# DSPcontrol.net
KiCad netlist of a schematic drawn in Altium Designer
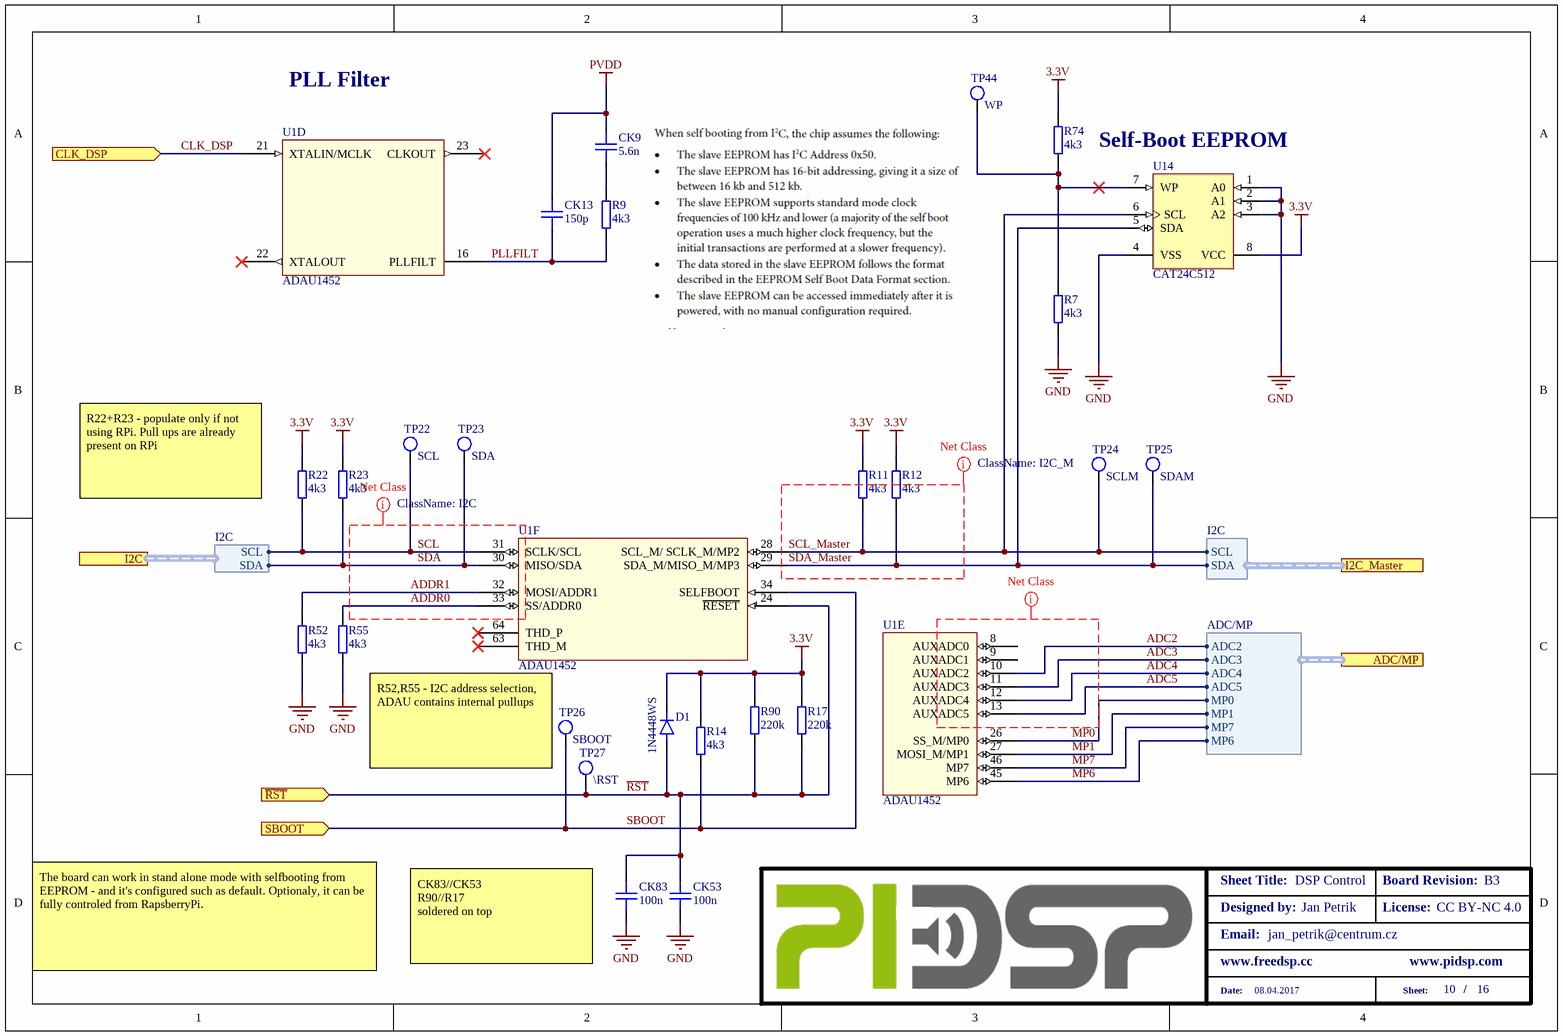
[diagram p0: DSPcontrol.SchDoc]

(export (version "E")
  (design (tool "Eeschema 10.0.6"))
  (components
    (comp (ref "CK9")
      (value "5.6n")
      (footprint "CAPC1608X09N(SMC0603)")
      (description "MLCC")
      (fields
        (field (name "TOLERANCE") "10%")
        (field (name "VOLTAGE") "50V")
        (field (name "AUTHOR") "JP/27.03.2014")
      )
      (libsource (lib "JP_C") (part "5.6n-50V-0603-X7R"))
    )
    (comp (ref "CK13")
      (value "150p")
      (footprint "CAPC1608X09N(SMC0603)")
      (description "MLCC")
      (fields
        (field (name "TOLERANCE") "10%")
        (field (name "VOLTAGE") "50V")
        (field (name "AUTHOR") "JP/27.03.2014")
      )
      (libsource (lib "JP_C") (part "150p-50V-0603-NP0"))
    )
    (comp (ref "CK53")
      (value "100n")
      (footprint "CAPC1608X09N(SMC0603)")
      (description "MLCC")
      (fields
        (field (name "VOLTAGE") "50V")
        (field (name "TOLERANCE") "10%")
        (field (name "AUTHOR") "JP/27.03.2014")
      )
      (libsource (lib "JP_C") (part "100n-50V-0603-X7R"))
    )
    (comp (ref "CK83")
      (value "100n")
      (footprint "CAPC1608X09N(SMC0603)")
      (description "MLCC")
      (fields
        (field (name "VOLTAGE") "50V")
        (field (name "TOLERANCE") "10%")
        (field (name "AUTHOR") "JP/27.03.2014")
      )
      (libsource (lib "JP_C") (part "100n-50V-0603-X7R"))
    )
    (comp (ref "D1")
      (value "1N4448WS")
      (footprint "SOD-323")
      (description "Small signal diode")
      (fields (field (name "VOLTAGE") "75V"))
      (libsource (lib "JP_IC") (part "1N4448WS"))
    )
    (comp (ref "R7")
      (value "4k3")
      (footprint "RESC1608X06N(SMR0603)")
      (description "Chip Resistor")
      (fields (field (name "AUTHOR") "JP/10.06.2014"))
      (libsource (lib "JP_R") (part "4K3-100mW-0603-ThickFilm"))
    )
    (comp (ref "R9")
      (value "4k3")
      (footprint "RESC1608X06N(SMR0603)")
      (description "Chip Resistor")
      (fields (field (name "AUTHOR") "JP/10.06.2014"))
      (libsource (lib "JP_R") (part "4K3-100mW-0603-ThickFilm"))
    )
    (comp (ref "R11")
      (value "4k3")
      (footprint "RESC1608X06N(SMR0603)")
      (description "Chip Resistor")
      (fields (field (name "AUTHOR") "JP/10.06.2014"))
      (libsource (lib "JP_R") (part "4K3-100mW-0603-ThickFilm"))
    )
    (comp (ref "R12")
      (value "4k3")
      (footprint "RESC1608X06N(SMR0603)")
      (description "Chip Resistor")
      (fields (field (name "AUTHOR") "JP/10.06.2014"))
      (libsource (lib "JP_R") (part "4K3-100mW-0603-ThickFilm"))
    )
    (comp (ref "R14")
      (value "4k3")
      (footprint "RESC1608X06N(SMR0603)")
      (description "Chip Resistor")
      (fields (field (name "AUTHOR") "JP/10.06.2014"))
      (libsource (lib "JP_R") (part "4K3-100mW-0603-ThickFilm"))
    )
    (comp (ref "R17")
      (value "220k")
      (footprint "RESC1608X06N(SMR0603)")
      (description "Chip Resistor")
      (fields (field (name "AUTHOR") "JP/10.06.2014"))
      (libsource (lib "JP_R") (part "220k-100mW-0603-ThickFilm"))
    )
    (comp (ref "R22")
      (value "4k3")
      (footprint "RESC1608X06N(SMR0603)")
      (description "Chip Resistor")
      (fields (field (name "AUTHOR") "JP/10.06.2014"))
      (libsource (lib "JP_R") (part "4K3-100mW-0603-ThickFilm"))
    )
    (comp (ref "R23")
      (value "4k3")
      (footprint "RESC1608X06N(SMR0603)")
      (description "Chip Resistor")
      (fields (field (name "AUTHOR") "JP/10.06.2014"))
      (libsource (lib "JP_R") (part "4K3-100mW-0603-ThickFilm"))
    )
    (comp (ref "R52")
      (value "4k3")
      (footprint "RESC1608X06N(SMR0603)")
      (description "Chip Resistor")
      (fields (field (name "AUTHOR") "JP/10.06.2014"))
      (libsource (lib "JP_R") (part "4K3-100mW-0603-ThickFilm"))
    )
    (comp (ref "R55")
      (value "4k3")
      (footprint "RESC1608X06N(SMR0603)")
      (description "Chip Resistor")
      (fields (field (name "AUTHOR") "JP/10.06.2014"))
      (libsource (lib "JP_R") (part "4K3-100mW-0603-ThickFilm"))
    )
    (comp (ref "R74")
      (value "4k3")
      (footprint "RESC1608X06N(SMR0603)")
      (description "Chip Resistor")
      (fields (field (name "AUTHOR") "JP/10.06.2014"))
      (libsource (lib "JP_R") (part "4K3-100mW-0603-ThickFilm"))
    )
    (comp (ref "R90")
      (value "220k")
      (footprint "RESC1608X06N(SMR0603)")
      (description "Chip Resistor")
      (fields (field (name "AUTHOR") "JP/10.06.2014"))
      (libsource (lib "JP_R") (part "220k-100mW-0603-ThickFilm"))
    )
    (comp (ref "TP22")
      (value "SCL")
      (footprint "TP_0.8/0.4_ROUND")
      (description "Testpoint - VIA")
      (libsource (lib "JP_CONN") (part "TEST_POINT_VIA"))
    )
    (comp (ref "TP23")
      (value "SDA")
      (footprint "TP_0.8/0.4_ROUND")
      (description "Testpoint - VIA")
      (libsource (lib "JP_CONN") (part "TEST_POINT_VIA"))
    )
    (comp (ref "TP24")
      (value "SCLM")
      (footprint "TP_0.8/0.4_ROUND")
      (description "Testpoint - VIA")
      (libsource (lib "JP_CONN") (part "TEST_POINT_VIA"))
    )
    (comp (ref "TP25")
      (value "SDAM")
      (footprint "TP_0.8/0.4_ROUND")
      (description "Testpoint - VIA")
      (libsource (lib "JP_CONN") (part "TEST_POINT_VIA"))
    )
    (comp (ref "TP26")
      (value "SBOOT")
      (footprint "TP_0.8/0.4_ROUND")
      (description "Testpoint - VIA")
      (libsource (lib "JP_CONN") (part "TEST_POINT_VIA"))
    )
    (comp (ref "TP27")
      (value "RST")
      (footprint "TP_0.8/0.4_ROUND")
      (description "Testpoint - VIA")
      (libsource (lib "JP_CONN") (part "TEST_POINT_VIA"))
    )
    (comp (ref "TP44")
      (value "WP")
      (footprint "TP_0.8/0.4_ROUND")
      (description "Testpoint - VIA")
      (libsource (lib "JP_CONN") (part "TEST_POINT_VIA"))
    )
    (comp (ref "U1")
      (value "ADAU1452")
      (footprint "CP_72_6-handsoldering")
      (libsource (lib "JP_IC") (part "ADAU1452"))
    )
    (comp (ref "U14")
      (value "CAT24C512")
      (footprint "SOIC127P600X175-8N(SOIC_8)")
      (description "512 Kb I2C CMOS Serial  EEPROM")
      (libsource (lib "JP_IC") (part "CAT24C512"))
    )
  )
  (nets
    (net (code "3") (name "/ADC2") (class "Default")
      (node (ref "U1") (pin "10") (pinfunction "AUXADC2_10") (pintype "bidirectional"))
    )
    (net (code "4") (name "/ADC3") (class "Default")
      (node (ref "U1") (pin "11") (pinfunction "AUXADC3_11") (pintype "bidirectional"))
    )
    (net (code "5") (name "/ADC4") (class "Default")
      (node (ref "U1") (pin "12") (pinfunction "AUXADC4_12") (pintype "bidirectional"))
    )
    (net (code "6") (name "/ADC5") (class "Default")
      (node (ref "U1") (pin "13") (pinfunction "AUXADC5_13") (pintype "bidirectional"))
    )
    (net (code "7") (name "/ADDR0") (class "Default")
      (node (ref "R55") (pin "2") (pinfunction "2_2") (pintype "passive"))
      (node (ref "U1") (pin "33") (pinfunction "SS/ADDR0_33") (pintype "bidirectional"))
    )
    (net (code "8") (name "/ADDR1") (class "Default")
      (node (ref "R52") (pin "2") (pinfunction "2_2") (pintype "passive"))
      (node (ref "U1") (pin "32") (pinfunction "MOSI/ADDR1_32") (pintype "bidirectional"))
    )
    (net (code "9") (name "/CLK_DSP") (class "Default")
      (node (ref "U1") (pin "21") (pinfunction "XTALIN/MCLK_21") (pintype "input"))
    )
    (net (code "10") (name "/MP0") (class "Default")
      (node (ref "U1") (pin "26") (pinfunction "SS_M/MP0_26") (pintype "bidirectional"))
    )
    (net (code "11") (name "/MP1") (class "Default")
      (node (ref "U1") (pin "27") (pinfunction "MOSI_M/MP1_27") (pintype "bidirectional"))
    )
    (net (code "12") (name "/MP6") (class "Default")
      (node (ref "U1") (pin "45") (pinfunction "MP6_45") (pintype "bidirectional"))
    )
    (net (code "13") (name "/MP7") (class "Default")
      (node (ref "U1") (pin "46") (pinfunction "MP7_46") (pintype "bidirectional"))
    )
    (net (code "14") (name "/PLLFILT") (class "Default")
      (node (ref "CK13") (pin "2") (pinfunction "2_2") (pintype "passive"))
      (node (ref "R9") (pin "1") (pinfunction "1_1") (pintype "passive"))
      (node (ref "U1") (pin "16") (pinfunction "PLLFILT_16") (pintype "passive"))
    )
    (net (code "15") (name "/SBOOT") (class "Default")
      (node (ref "R14") (pin "1") (pinfunction "1_1") (pintype "passive"))
      (node (ref "TP26") (pin "1") (pintype "passive"))
      (node (ref "U1") (pin "34") (pinfunction "SELFBOOT_34") (pintype "input"))
    )
    (net (code "16") (name "/SCL") (class "Default")
      (node (ref "R22") (pin "1") (pinfunction "1_1") (pintype "passive"))
      (node (ref "TP22") (pin "1") (pintype "passive"))
      (node (ref "U1") (pin "31") (pinfunction "SCLK/SCL_31") (pintype "bidirectional"))
    )
    (net (code "17") (name "/SCL_Master") (class "Default")
      (node (ref "R11") (pin "1") (pinfunction "1_1") (pintype "passive"))
      (node (ref "TP24") (pin "1") (pintype "passive"))
      (node (ref "U1") (pin "28") (pinfunction "SCL_M/_SCLK_M/MP2_28") (pintype "bidirectional"))
      (node (ref "U14") (pin "6") (pinfunction "SCL_6") (pintype "input"))
    )
    (net (code "18") (name "/SDA") (class "Default")
      (node (ref "R23") (pin "1") (pinfunction "1_1") (pintype "passive"))
      (node (ref "TP23") (pin "1") (pintype "passive"))
      (node (ref "U1") (pin "30") (pinfunction "MISO/SDA_30") (pintype "bidirectional"))
    )
    (net (code "19") (name "/SDA_Master") (class "Default")
      (node (ref "R12") (pin "1") (pinfunction "1_1") (pintype "passive"))
      (node (ref "TP25") (pin "1") (pintype "passive"))
      (node (ref "U1") (pin "29") (pinfunction "SDA_M/MISO_M/MP3_29") (pintype "bidirectional"))
      (node (ref "U14") (pin "5") (pinfunction "SDA_5") (pintype "bidirectional"))
    )
    (net (code "22") (name "/~{RST}") (class "Default")
      (node (ref "CK53") (pin "1") (pinfunction "1_1") (pintype "passive"))
      (node (ref "CK83") (pin "1") (pinfunction "1_1") (pintype "passive"))
      (node (ref "D1") (pin "2") (pinfunction "A_2") (pintype "passive"))
      (node (ref "R17") (pin "1") (pinfunction "1_1") (pintype "passive"))
      (node (ref "R90") (pin "1") (pinfunction "1_1") (pintype "passive"))
      (node (ref "TP27") (pin "1") (pintype "passive"))
      (node (ref "U1") (pin "24") (pinfunction "~{RESET}_24") (pintype "input"))
    )
    (net (code "23") (name "3.3V") (class "Default")
      (node (ref "D1") (pin "1") (pinfunction "C_1") (pintype "passive"))
      (node (ref "R11") (pin "2") (pinfunction "2_2") (pintype "passive"))
      (node (ref "R12") (pin "2") (pinfunction "2_2") (pintype "passive"))
      (node (ref "R14") (pin "2") (pinfunction "2_2") (pintype "passive"))
      (node (ref "R17") (pin "2") (pinfunction "2_2") (pintype "passive"))
      (node (ref "R22") (pin "2") (pinfunction "2_2") (pintype "passive"))
      (node (ref "R23") (pin "2") (pinfunction "2_2") (pintype "passive"))
      (node (ref "R74") (pin "2") (pinfunction "2_2") (pintype "passive"))
      (node (ref "R90") (pin "2") (pinfunction "2_2") (pintype "passive"))
      (node (ref "U14") (pin "8") (pinfunction "VCC_8") (pintype "power_in"))
    )
    (net (code "24") (name "GND") (class "Default")
      (node (ref "CK53") (pin "2") (pinfunction "2_2") (pintype "passive"))
      (node (ref "CK83") (pin "2") (pinfunction "2_2") (pintype "passive"))
      (node (ref "R52") (pin "1") (pinfunction "1_1") (pintype "passive"))
      (node (ref "R55") (pin "1") (pinfunction "1_1") (pintype "passive"))
      (node (ref "R7") (pin "1") (pinfunction "1_1") (pintype "passive"))
      (node (ref "U14") (pin "1") (pinfunction "A0_1") (pintype "input"))
      (node (ref "U14") (pin "2") (pinfunction "A1_2") (pintype "input"))
      (node (ref "U14") (pin "3") (pinfunction "A2_3") (pintype "input"))
      (node (ref "U14") (pin "4") (pinfunction "VSS_4") (pintype "power_in"))
    )
    (net (code "25") (name "Net-(CK9-Pad2)") (class "Default")
      (node (ref "CK9") (pin "2") (pinfunction "2_2") (pintype "passive"))
      (node (ref "R9") (pin "2") (pinfunction "2_2") (pintype "passive"))
    )
    (net (code "26") (name "Net-(U14-WP)") (class "Default")
      (node (ref "R7") (pin "2") (pinfunction "2_2") (pintype "passive"))
      (node (ref "R74") (pin "1") (pinfunction "1_1") (pintype "passive"))
      (node (ref "TP44") (pin "1") (pintype "passive"))
      (node (ref "U14") (pin "7") (pinfunction "WP_7") (pintype "input"))
    )
    (net (code "27") (name "PVDD") (class "Default")
      (node (ref "CK13") (pin "1") (pinfunction "1_1") (pintype "passive"))
      (node (ref "CK9") (pin "1") (pinfunction "1_1") (pintype "passive"))
    )
    (net (code "28") (name "unconnected-(U1D-CLKOUT-Pad23)") (class "Default")
      (node (ref "U1") (pin "23") (pinfunction "CLKOUT_23") (pintype "output+no_connect"))
    )
    (net (code "29") (name "unconnected-(U1D-XTALOUT-Pad22)") (class "Default")
      (node (ref "U1") (pin "22") (pinfunction "XTALOUT_22") (pintype "output+no_connect"))
    )
    (net (code "30") (name "unconnected-(U1E-AUXADC0-Pad8)") (class "Default")
      (node (ref "U1") (pin "8") (pinfunction "AUXADC0_8") (pintype "bidirectional"))
    )
    (net (code "31") (name "unconnected-(U1E-AUXADC1-Pad9)") (class "Default")
      (node (ref "U1") (pin "9") (pinfunction "AUXADC1_9") (pintype "bidirectional"))
    )
    (net (code "32") (name "unconnected-(U1F-THD_M-Pad63)") (class "Default")
      (node (ref "U1") (pin "63") (pinfunction "THD_M_63") (pintype "passive+no_connect"))
    )
    (net (code "33") (name "unconnected-(U1F-THD_P-Pad64)") (class "Default")
      (node (ref "U1") (pin "64") (pinfunction "THD_P_64") (pintype "passive+no_connect"))
    )
  )
)
